# Sheet2.net
KiCad netlist of a schematic drawn in Altium Designer
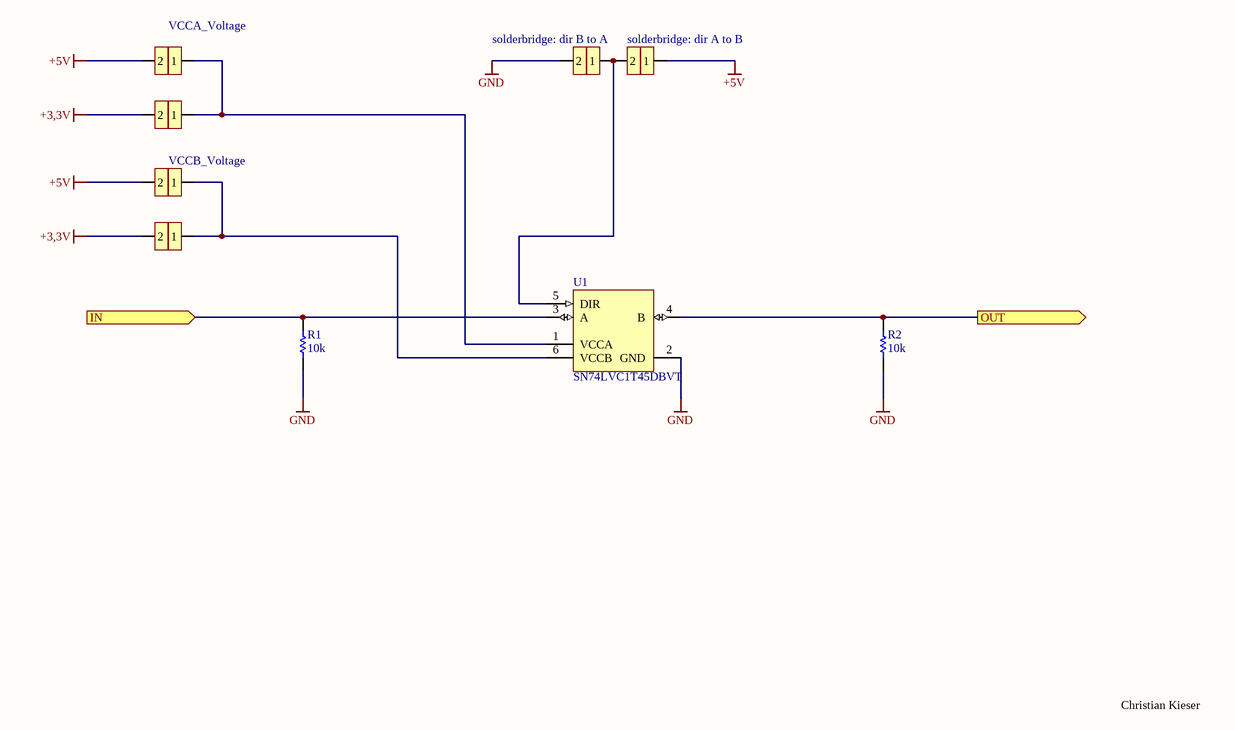
[diagram p0: Sheet2.SchDoc]

(export (version "E")
  (design (tool "Eeschema 10.0.6"))
  (components
    (comp (ref "J1")
      (value "normal solderbridge")
      (footprint "PCBComponent")
      (libsource (lib "Altium Vault EMBL 3") (part "CMP-001-0133-A.1"))
    )
    (comp (ref "J3")
      (value "normal solderbridge")
      (footprint "PCBComponent")
      (libsource (lib "Altium Vault EMBL 3") (part "CMP-001-0133-A.1"))
    )
    (comp (ref "J4")
      (value "normal solderbridge")
      (footprint "PCBComponent")
      (libsource (lib "Altium Vault EMBL 3") (part "CMP-001-0133-A.1"))
    )
    (comp (ref "J6")
      (value "normal solderbridge")
      (footprint "PCBComponent")
      (libsource (lib "Altium Vault EMBL 3") (part "CMP-001-0133-A.1"))
    )
    (comp (ref "J7")
      (value "normal solderbridge")
      (footprint "PCBComponent")
      (libsource (lib "Altium Vault EMBL 3") (part "CMP-001-0133-A.1"))
    )
    (comp (ref "J8")
      (value "normal solderbridge")
      (footprint "PCBComponent")
      (libsource (lib "Altium Vault EMBL 3") (part "CMP-001-0133-A.1"))
    )
    (comp (ref "R1")
      (value "10k")
      (footprint "YAGO-RC0805_M")
      (description "0805 Yageo Standard BlackBox Resistors")
      (fields (field (name "TOLERANCE") "±1%") (field (name "MANUFACTURER") "Yageo"))
      (libsource (lib "Altium Vault EMBL 3") (part "CMP-001-0027-2"))
    )
    (comp (ref "R2")
      (value "10k")
      (footprint "YAGO-RC0805_M")
      (description "0805 Yageo Standard BlackBox Resistors")
      (fields (field (name "TOLERANCE") "±1%") (field (name "MANUFACTURER") "Yageo"))
      (libsource (lib "Altium Vault EMBL") (part "CMP-001-0027-2"))
    )
    (comp (ref "U1")
      (value "SN74LVC1T45DBVT")
      (footprint "DBV0006A_M")
      (fields
        (field (name "MANUFACTURER") "Texas Instruments")
        (field (name "GENERIC PART NUMBER") "SN74LVC1T45")
      )
      (libsource (lib "Altium Vault EMBL 3") (part "CMP-00491-1"))
    )
  )
  (nets
    (net (code "1") (name "+3,3V") (class "Default")
      (node (ref "J3") (pin "2") (pinfunction "2_2") (pintype "passive"))
      (node (ref "J6") (pin "2") (pinfunction "2_2") (pintype "passive"))
    )
    (net (code "2") (name "+5V") (class "Default")
      (node (ref "J1") (pin "2") (pinfunction "2_2") (pintype "passive"))
      (node (ref "J4") (pin "2") (pinfunction "2_2") (pintype "passive"))
      (node (ref "J8") (pin "1") (pinfunction "1_1") (pintype "passive"))
    )
    (net (code "3") (name "/IN") (class "Default")
      (node (ref "R1") (pin "2") (pinfunction "2_2") (pintype "passive"))
      (node (ref "U1") (pin "3") (pinfunction "A_3") (pintype "bidirectional"))
    )
    (net (code "4") (name "/OUT") (class "Default")
      (node (ref "R2") (pin "2") (pinfunction "2_2") (pintype "passive"))
      (node (ref "U1") (pin "4") (pinfunction "B_4") (pintype "bidirectional"))
    )
    (net (code "5") (name "GND") (class "Default")
      (node (ref "J7") (pin "2") (pinfunction "2_2") (pintype "passive"))
      (node (ref "R1") (pin "1") (pinfunction "1_1") (pintype "passive"))
      (node (ref "R2") (pin "1") (pinfunction "1_1") (pintype "passive"))
      (node (ref "U1") (pin "2") (pinfunction "GND_2") (pintype "power_in"))
    )
    (net (code "6") (name "Net-(U1-DIR)") (class "Default")
      (node (ref "J7") (pin "1") (pinfunction "1_1") (pintype "passive"))
      (node (ref "J8") (pin "2") (pinfunction "2_2") (pintype "passive"))
      (node (ref "U1") (pin "5") (pinfunction "DIR_5") (pintype "input"))
    )
    (net (code "7") (name "Net-(U1-VCCA)") (class "Default")
      (node (ref "J1") (pin "1") (pinfunction "1_1") (pintype "passive"))
      (node (ref "J3") (pin "1") (pinfunction "1_1") (pintype "passive"))
      (node (ref "U1") (pin "1") (pinfunction "VCCA_1") (pintype "power_in"))
    )
    (net (code "8") (name "Net-(U1-VCCB)") (class "Default")
      (node (ref "J4") (pin "1") (pinfunction "1_1") (pintype "passive"))
      (node (ref "J6") (pin "1") (pinfunction "1_1") (pintype "passive"))
      (node (ref "U1") (pin "6") (pinfunction "VCCB_6") (pintype "power_in"))
    )
  )
)
